# LEDs.net
KiCad netlist of a schematic drawn in Altium Designer
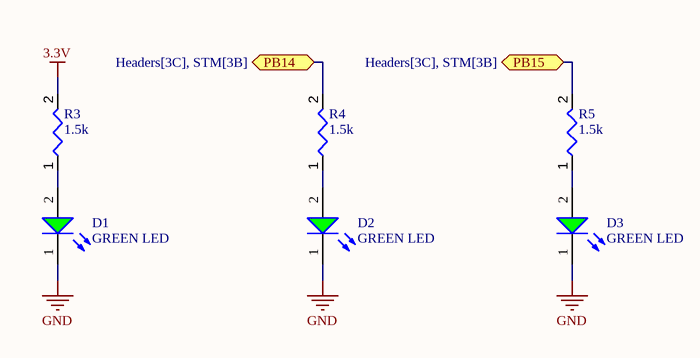
[diagram p0: LEDs.SchDoc]

(export (version "E")
  (design (tool "Eeschema 10.0.6"))
  (components
    (comp (ref "D1")
      (value "GREEN LED")
      (footprint "WL-SMCW_0603_150060xx75000")
      (description "Single Color LED, Green, Water Clear, 1.1mm")
      (libsource (lib "Jack Bolte") (part "CMP-007-00046-2"))
    )
    (comp (ref "D2")
      (value "GREEN LED")
      (footprint "WL-SMCW_0603_150060xx75000")
      (description "Single Color LED, Green, Water Clear, 1.1mm")
      (libsource (lib "Jack Bolte") (part "CMP-007-00046-2"))
    )
    (comp (ref "D3")
      (value "GREEN LED")
      (footprint "WL-SMCW_0603_150060xx75000")
      (description "Single Color LED, Green, Water Clear, 1.1mm")
      (libsource (lib "Jack Bolte") (part "CMP-007-00046-2"))
    )
    (comp (ref "R3")
      (value "1.5k")
      (footprint "RES_0603")
      (description "Resistor 1.5k 5% 100 mW 0603")
      (fields (field (name "TOLERANCE") "5%") (field (name "POWER") "100mW"))
      (libsource (lib "Jack Bolte") (part "[0402] RES 3.3k"))
    )
    (comp (ref "R4")
      (value "1.5k")
      (footprint "RES_0603")
      (description "Resistor 1.5k 5% 100 mW 0603")
      (fields (field (name "TOLERANCE") "5%") (field (name "POWER") "100mW"))
      (libsource (lib "Jack Bolte") (part "[0402] RES 3.3k"))
    )
    (comp (ref "R5")
      (value "1.5k")
      (footprint "RES_0603")
      (description "Resistor 1.5k 5% 100 mW 0603")
      (fields (field (name "TOLERANCE") "5%") (field (name "POWER") "100mW"))
      (libsource (lib "Jack Bolte") (part "[0402] RES 3.3k"))
    )
  )
  (nets
    (net (code "1") (name "/PB14") (class "Default")
      (node (ref "R4") (pin "2") (pinfunction "2_2") (pintype "passive"))
    )
    (net (code "2") (name "/PB15") (class "Default")
      (node (ref "R5") (pin "2") (pinfunction "2_2") (pintype "passive"))
    )
    (net (code "3") (name "3.3V") (class "Default")
      (node (ref "R3") (pin "2") (pinfunction "2_2") (pintype "passive"))
    )
    (net (code "4") (name "GND") (class "Default")
      (node (ref "D1") (pin "1") (pinfunction "K_1") (pintype "passive"))
      (node (ref "D2") (pin "1") (pinfunction "K_1") (pintype "passive"))
      (node (ref "D3") (pin "1") (pinfunction "K_1") (pintype "passive"))
    )
    (net (code "5") (name "Net-(D1-A)") (class "Default")
      (node (ref "D1") (pin "2") (pinfunction "A_2") (pintype "passive"))
      (node (ref "R3") (pin "1") (pinfunction "1_1") (pintype "passive"))
    )
    (net (code "6") (name "Net-(D2-A)") (class "Default")
      (node (ref "D2") (pin "2") (pinfunction "A_2") (pintype "passive"))
      (node (ref "R4") (pin "1") (pinfunction "1_1") (pintype "passive"))
    )
    (net (code "7") (name "Net-(D3-A)") (class "Default")
      (node (ref "D3") (pin "2") (pinfunction "A_2") (pintype "passive"))
      (node (ref "R5") (pin "1") (pinfunction "1_1") (pintype "passive"))
    )
  )
)
